# B293A_Monitor.net
KiCad netlist of a schematic drawn in Altium Designer
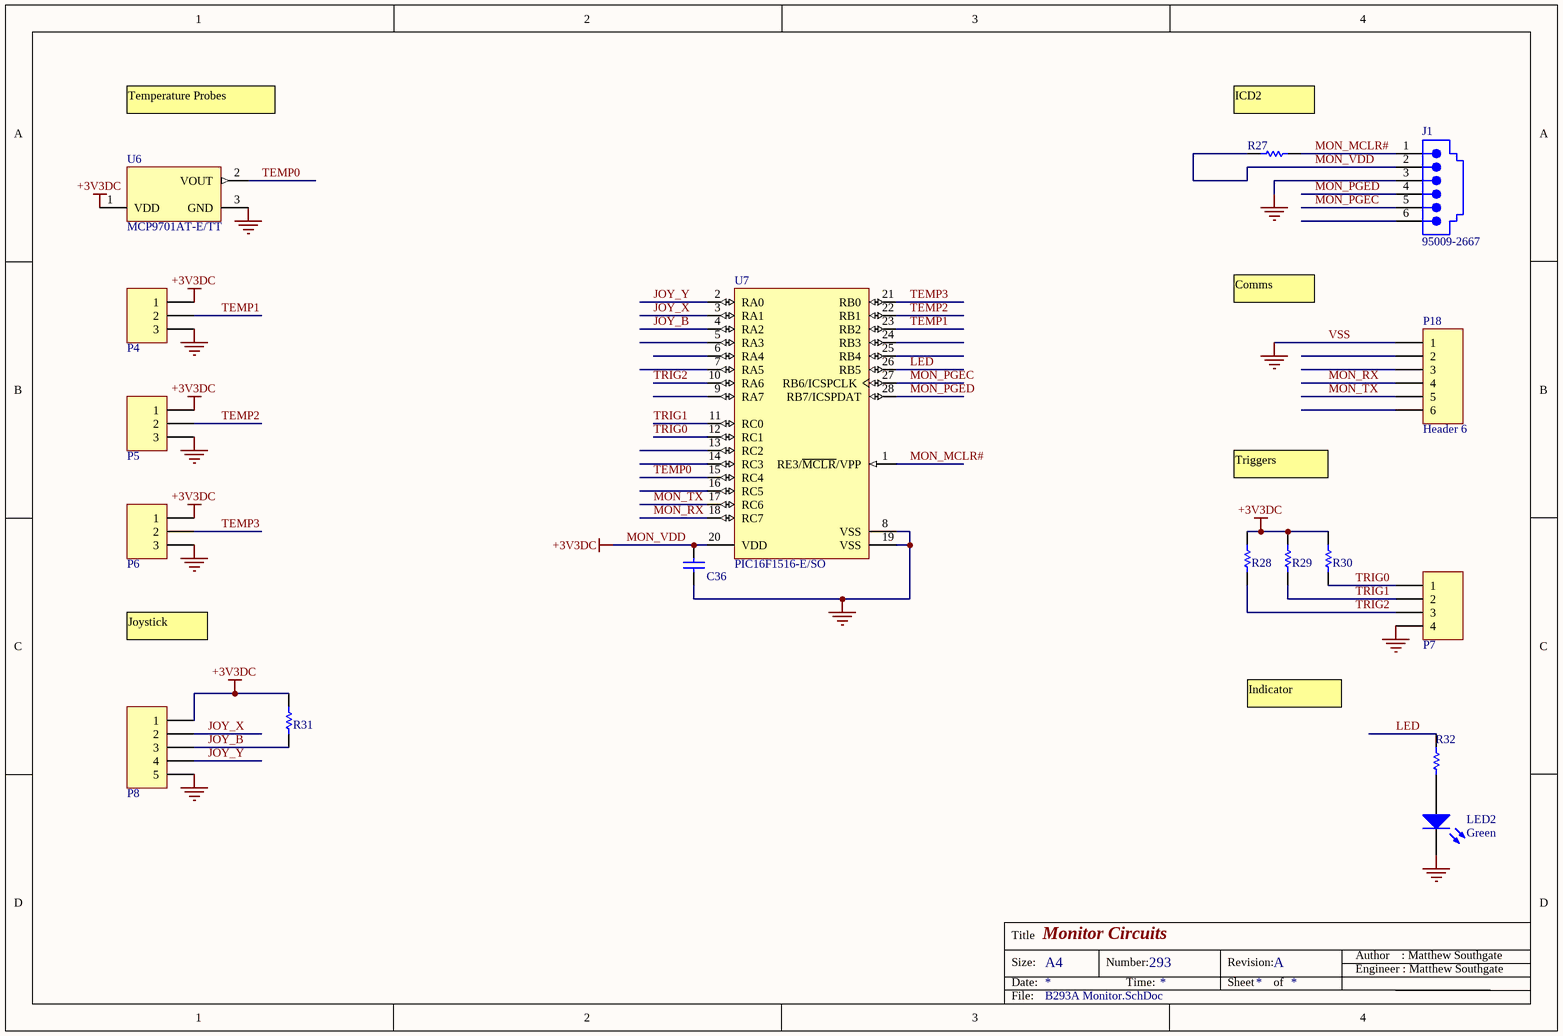
[diagram p0: B293A Monitor.SchDoc]

(export (version "E")
  (design (tool "Eeschema 10.0.6"))
  (components
    (comp (ref "C36")
      (value "CAP 120nF 50V 0805(2012)")
      (footprint "CAPC0805(2012)145_N")
      (description "CAP 120nF 50V ±20% 0805 (2012 Metric) Thickness 1.45mm SMD")
      (fields (field (name "TOLERANCE") "±20%"))
      (libsource (lib "Altium Content Vault") (part "CAP"))
    )
    (comp (ref "J1")
      (value "95009-2667")
      (footprint "95009-2667")
      (description "Right Angle, Standard Profile, Flush Mount PCB Jack")
      (fields (field (name "MANUFACTURER") "MOLEX") (field (name "PUBLISHER") "Altium Limited"))
      (libsource (lib "Matt SCH Library") (part "95009-2667"))
    )
    (comp (ref "LED2")
      (value "Green")
      (footprint "Matt PCB Library:1206 - LED")
      (description "LED, SMD, 1206, CLR LENS, GREEN")
      (fields
        (field (name "MANUFACTURER PART NUMBER") "KPC-3216SGC")
        (field (name "MANUFACTURER") "KINGBRIGHT")
      )
      (libsource (lib "Matt SCH Library") (part "LED 1206 GREEN"))
    )
    (comp (ref "P4")
      (value "MOLEX SL 3W VERT")
      (footprint "MOLEX SL 3W Vertical with latch")
      (description "MOLEX - 70543-0037 - WIRE-BOARD CONNECTOR HEADER 3POS, 2.54MM")
      (fields (field (name "MANUFACTURER PART NUMBER") "70543-0037"))
      (libsource (lib "Matt SCH Library") (part "MOLEX SL 3W VERT"))
    )
    (comp (ref "P5")
      (value "MOLEX SL 3W VERT")
      (footprint "MOLEX SL 3W Vertical with latch")
      (description "MOLEX - 70543-0037 - WIRE-BOARD CONNECTOR HEADER 3POS, 2.54MM")
      (fields (field (name "MANUFACTURER PART NUMBER") "70543-0037"))
      (libsource (lib "Matt SCH Library") (part "MOLEX SL 3W VERT"))
    )
    (comp (ref "P6")
      (value "MOLEX SL 3W VERT")
      (footprint "MOLEX SL 3W Vertical with latch")
      (description "MOLEX - 70543-0037 - WIRE-BOARD CONNECTOR HEADER 3POS, 2.54MM")
      (fields (field (name "MANUFACTURER PART NUMBER") "70543-0037"))
      (libsource (lib "Matt SCH Library") (part "MOLEX SL 3W VERT"))
    )
    (comp (ref "P7")
      (value "MOLEX SL 4W VERT")
      (footprint "MOLEX SL 4W Vertical with latch")
      (description "MOLEX - 70543-0108 - CONNECTOR, HEADER, 4POS, 1ROW, 2.54MM")
      (fields (field (name "MANUFACTURER PART NUMBER") "70543-0108"))
      (libsource (lib "Matt SCH Library") (part "MOLEX SL 4W VERT"))
    )
    (comp (ref "P8")
      (value "MOLEX SL 5W VERT")
      (footprint "MOLEX SL 5W Vertical with latch")
      (description "MOLEX - 70543-0004 - CONNECTOR, HEADER, 5POS, 1ROW, 2.54MM")
      (fields (field (name "MANUFACTURER PART NUMBER") "70543-0004"))
      (libsource (lib "Matt SCH Library") (part "MOLEX SL 5W VERT"))
    )
    (comp (ref "P18")
      (value "Header 6")
      (footprint "HDR1X6")
      (description "Header, 6-Pin")
      (fields (field (name "PUBLISHER") "Altium Limited"))
      (libsource (lib "Miscellaneous Connectors") (part "Header 6"))
    )
    (comp (ref "R27")
      (value "10K 5% 0805(2012)")
      (footprint "RESC0805(2012)_L")
      (description "10K 0.125W 5% 0805 (2012 Metric)  SMD")
      (fields (field (name "POWER") "0.125 W") (field (name "TOLERANCE") "5 %"))
      (libsource (lib "Altium Content Vault") (part "RES"))
    )
    (comp (ref "R28")
      (value "10K 5% 0805(2012)")
      (footprint "RESC0805(2012)_L")
      (description "10K 0.125W 5% 0805 (2012 Metric)  SMD")
      (fields (field (name "POWER") "0.125 W") (field (name "TOLERANCE") "5 %"))
      (libsource (lib "Altium Content Vault") (part "RES"))
    )
    (comp (ref "R29")
      (value "10K 5% 0805(2012)")
      (footprint "RESC0805(2012)_L")
      (description "10K 0.125W 5% 0805 (2012 Metric)  SMD")
      (fields (field (name "POWER") "0.125 W") (field (name "TOLERANCE") "5 %"))
      (libsource (lib "Altium Content Vault") (part "RES"))
    )
    (comp (ref "R30")
      (value "10K 5% 0805(2012)")
      (footprint "RESC0805(2012)_L")
      (description "10K 0.125W 5% 0805 (2012 Metric)  SMD")
      (fields (field (name "POWER") "0.125 W") (field (name "TOLERANCE") "5 %"))
      (libsource (lib "Altium Content Vault") (part "RES"))
    )
    (comp (ref "R31")
      (value "10K 5% 0805(2012)")
      (footprint "RESC0805(2012)_L")
      (description "10K 0.125W 5% 0805 (2012 Metric)  SMD")
      (fields (field (name "POWER") "0.125 W") (field (name "TOLERANCE") "5 %"))
      (libsource (lib "Altium Content Vault") (part "RES"))
    )
    (comp (ref "R32")
      (value "1K 5% 0805(2012)")
      (footprint "RESC0805(2012)_N")
      (description "1K 0.125W 5% 0805 (2012 Metric)  SMD")
      (fields (field (name "TOLERANCE") "5 %") (field (name "POWER") "0.125 W"))
      (libsource (lib "Altium Content Vault") (part "RES"))
    )
    (comp (ref "U6")
      (value "MCP9701AT-E/TT")
      (footprint "SOT-23-TT3_M")
      (description "Low-Power Linear Active Thermistor IC, 3-Pin SOT-23, Extended Temperature, Tape and Reel")
      (libsource (lib "Altium Content Vault") (part "CMP-0192-00221-1"))
    )
    (comp (ref "U7")
      (value "PIC16F1516-E/SO")
      (footprint "MCHP-SOIC-SO28_N")
      (fields (field (name "MANUFACTURER") "Microchip"))
      (libsource (lib "Altium Content Vault") (part "MCHP-PIC16XF151XX_178X-28"))
    )
  )
  (nets
    (net (code "1") (name "+3V3DC") (class "Default")
      (node (ref "C36") (pin "1") (pinfunction "1_1") (pintype "passive"))
      (node (ref "J1") (pin "2") (pinfunction "2_2") (pintype "passive"))
      (node (ref "P4") (pin "1") (pinfunction "1_1") (pintype "passive"))
      (node (ref "P5") (pin "1") (pinfunction "1_1") (pintype "passive"))
      (node (ref "P6") (pin "1") (pinfunction "1_1") (pintype "passive"))
      (node (ref "P8") (pin "1") (pinfunction "1_1") (pintype "passive"))
      (node (ref "R27") (pin "1") (pinfunction "1_1") (pintype "passive"))
      (node (ref "R28") (pin "2") (pinfunction "2_2") (pintype "passive"))
      (node (ref "R29") (pin "2") (pinfunction "2_2") (pintype "passive"))
      (node (ref "R30") (pin "2") (pinfunction "2_2") (pintype "passive"))
      (node (ref "R31") (pin "2") (pinfunction "2_2") (pintype "passive"))
      (node (ref "U6") (pin "1") (pinfunction "VDD_1") (pintype "power_in"))
      (node (ref "U7") (pin "20") (pinfunction "VDD_20") (pintype "power_in"))
    )
    (net (code "2") (name "/JOY_B") (class "Default")
      (node (ref "P8") (pin "3") (pinfunction "3_3") (pintype "passive"))
      (node (ref "R31") (pin "1") (pinfunction "1_1") (pintype "passive"))
      (node (ref "U7") (pin "4") (pinfunction "RA2_4") (pintype "bidirectional"))
    )
    (net (code "3") (name "/JOY_X") (class "Default")
      (node (ref "P8") (pin "2") (pinfunction "2_2") (pintype "passive"))
      (node (ref "U7") (pin "3") (pinfunction "RA1_3") (pintype "bidirectional"))
    )
    (net (code "4") (name "/JOY_Y") (class "Default")
      (node (ref "P8") (pin "4") (pinfunction "4_4") (pintype "passive"))
      (node (ref "U7") (pin "2") (pinfunction "RA0_2") (pintype "bidirectional"))
    )
    (net (code "5") (name "/LED") (class "Default")
      (node (ref "R32") (pin "2") (pinfunction "2_2") (pintype "passive"))
      (node (ref "U7") (pin "26") (pinfunction "RB5_26") (pintype "bidirectional"))
    )
    (net (code "6") (name "/MON_MCLR#") (class "Default")
      (node (ref "J1") (pin "1") (pinfunction "1_1") (pintype "passive"))
      (node (ref "R27") (pin "2") (pinfunction "2_2") (pintype "passive"))
      (node (ref "U7") (pin "1") (pinfunction "RE3/~{MCLR}/VPP_1") (pintype "input"))
    )
    (net (code "7") (name "/MON_PGEC") (class "Default")
      (node (ref "J1") (pin "5") (pinfunction "5_5") (pintype "passive"))
      (node (ref "U7") (pin "27") (pinfunction "RB6/ICSPCLK_27") (pintype "bidirectional"))
    )
    (net (code "8") (name "/MON_PGED") (class "Default")
      (node (ref "J1") (pin "4") (pinfunction "4_4") (pintype "passive"))
      (node (ref "U7") (pin "28") (pinfunction "RB7/ICSPDAT_28") (pintype "bidirectional"))
    )
    (net (code "9") (name "/MON_RX") (class "Default")
      (node (ref "P18") (pin "4") (pinfunction "4_4") (pintype "passive"))
      (node (ref "U7") (pin "18") (pinfunction "RC7_18") (pintype "bidirectional"))
    )
    (net (code "10") (name "/MON_TX") (class "Default")
      (node (ref "P18") (pin "5") (pinfunction "5_5") (pintype "passive"))
      (node (ref "U7") (pin "17") (pinfunction "RC6_17") (pintype "bidirectional"))
    )
    (net (code "11") (name "/TEMP0") (class "Default")
      (node (ref "U6") (pin "2") (pinfunction "VOUT_2") (pintype "output"))
      (node (ref "U7") (pin "15") (pinfunction "RC4_15") (pintype "bidirectional"))
    )
    (net (code "12") (name "/TEMP1") (class "Default")
      (node (ref "P4") (pin "2") (pinfunction "2_2") (pintype "passive"))
      (node (ref "U7") (pin "23") (pinfunction "RB2_23") (pintype "bidirectional"))
    )
    (net (code "13") (name "/TEMP2") (class "Default")
      (node (ref "P5") (pin "2") (pinfunction "2_2") (pintype "passive"))
      (node (ref "U7") (pin "22") (pinfunction "RB1_22") (pintype "bidirectional"))
    )
    (net (code "14") (name "/TEMP3") (class "Default")
      (node (ref "P6") (pin "2") (pinfunction "2_2") (pintype "passive"))
      (node (ref "U7") (pin "21") (pinfunction "RB0_21") (pintype "bidirectional"))
    )
    (net (code "15") (name "/TRIG0") (class "Default")
      (node (ref "P7") (pin "1") (pinfunction "1_1") (pintype "passive"))
      (node (ref "R30") (pin "1") (pinfunction "1_1") (pintype "passive"))
      (node (ref "U7") (pin "12") (pinfunction "RC1_12") (pintype "bidirectional"))
    )
    (net (code "16") (name "/TRIG1") (class "Default")
      (node (ref "P7") (pin "2") (pinfunction "2_2") (pintype "passive"))
      (node (ref "R29") (pin "1") (pinfunction "1_1") (pintype "passive"))
      (node (ref "U7") (pin "11") (pinfunction "RC0_11") (pintype "bidirectional"))
    )
    (net (code "17") (name "/TRIG2") (class "Default")
      (node (ref "P7") (pin "3") (pinfunction "3_3") (pintype "passive"))
      (node (ref "R28") (pin "1") (pinfunction "1_1") (pintype "passive"))
      (node (ref "U7") (pin "10") (pinfunction "RA6_10") (pintype "bidirectional"))
    )
    (net (code "18") (name "GND") (class "Default")
      (node (ref "C36") (pin "2") (pinfunction "2_2") (pintype "passive"))
      (node (ref "J1") (pin "3") (pinfunction "3_3") (pintype "passive"))
      (node (ref "LED2") (pin "K") (pinfunction "K_K") (pintype "passive"))
      (node (ref "P18") (pin "1") (pinfunction "1_1") (pintype "passive"))
      (node (ref "P4") (pin "3") (pinfunction "3_3") (pintype "passive"))
      (node (ref "P5") (pin "3") (pinfunction "3_3") (pintype "passive"))
      (node (ref "P6") (pin "3") (pinfunction "3_3") (pintype "passive"))
      (node (ref "P7") (pin "4") (pinfunction "4_4") (pintype "passive"))
      (node (ref "P8") (pin "5") (pinfunction "5_5") (pintype "passive"))
      (node (ref "U6") (pin "3") (pinfunction "GND_3") (pintype "power_in"))
      (node (ref "U7") (pin "19") (pinfunction "VSS_19") (pintype "power_in"))
      (node (ref "U7") (pin "8") (pinfunction "VSS_8") (pintype "power_in"))
    )
    (net (code "19") (name "Net-(LED2-PadA)") (class "Default")
      (node (ref "LED2") (pin "A") (pinfunction "A_A") (pintype "passive"))
      (node (ref "R32") (pin "1") (pinfunction "1_1") (pintype "passive"))
    )
    (net (code "20") (name "unconnected-(J1-Pad6)") (class "Default")
      (node (ref "J1") (pin "6") (pinfunction "6_6") (pintype "passive"))
    )
    (net (code "21") (name "unconnected-(P18-Pad2)") (class "Default")
      (node (ref "P18") (pin "2") (pinfunction "2_2") (pintype "passive"))
    )
    (net (code "22") (name "unconnected-(P18-Pad3)") (class "Default")
      (node (ref "P18") (pin "3") (pinfunction "3_3") (pintype "passive"))
    )
    (net (code "23") (name "unconnected-(P18-Pad6)") (class "Default")
      (node (ref "P18") (pin "6") (pinfunction "6_6") (pintype "passive"))
    )
    (net (code "24") (name "unconnected-(U7-RA3-Pad5)") (class "Default")
      (node (ref "U7") (pin "5") (pinfunction "RA3_5") (pintype "bidirectional"))
    )
    (net (code "25") (name "unconnected-(U7-RA4-Pad6)") (class "Default")
      (node (ref "U7") (pin "6") (pinfunction "RA4_6") (pintype "bidirectional"))
    )
    (net (code "26") (name "unconnected-(U7-RA5-Pad7)") (class "Default")
      (node (ref "U7") (pin "7") (pinfunction "RA5_7") (pintype "bidirectional"))
    )
    (net (code "27") (name "unconnected-(U7-RA7-Pad9)") (class "Default")
      (node (ref "U7") (pin "9") (pinfunction "RA7_9") (pintype "bidirectional"))
    )
    (net (code "28") (name "unconnected-(U7-RB3-Pad24)") (class "Default")
      (node (ref "U7") (pin "24") (pinfunction "RB3_24") (pintype "bidirectional"))
    )
    (net (code "29") (name "unconnected-(U7-RB4-Pad25)") (class "Default")
      (node (ref "U7") (pin "25") (pinfunction "RB4_25") (pintype "bidirectional"))
    )
    (net (code "30") (name "unconnected-(U7-RC2-Pad13)") (class "Default")
      (node (ref "U7") (pin "13") (pinfunction "RC2_13") (pintype "bidirectional"))
    )
    (net (code "31") (name "unconnected-(U7-RC3-Pad14)") (class "Default")
      (node (ref "U7") (pin "14") (pinfunction "RC3_14") (pintype "bidirectional"))
    )
    (net (code "32") (name "unconnected-(U7-RC5-Pad16)") (class "Default")
      (node (ref "U7") (pin "16") (pinfunction "RC5_16") (pintype "bidirectional"))
    )
  )
)
